# FDC_Board_DualSlim.net
KiCad netlist of a schematic drawn in EAGLE
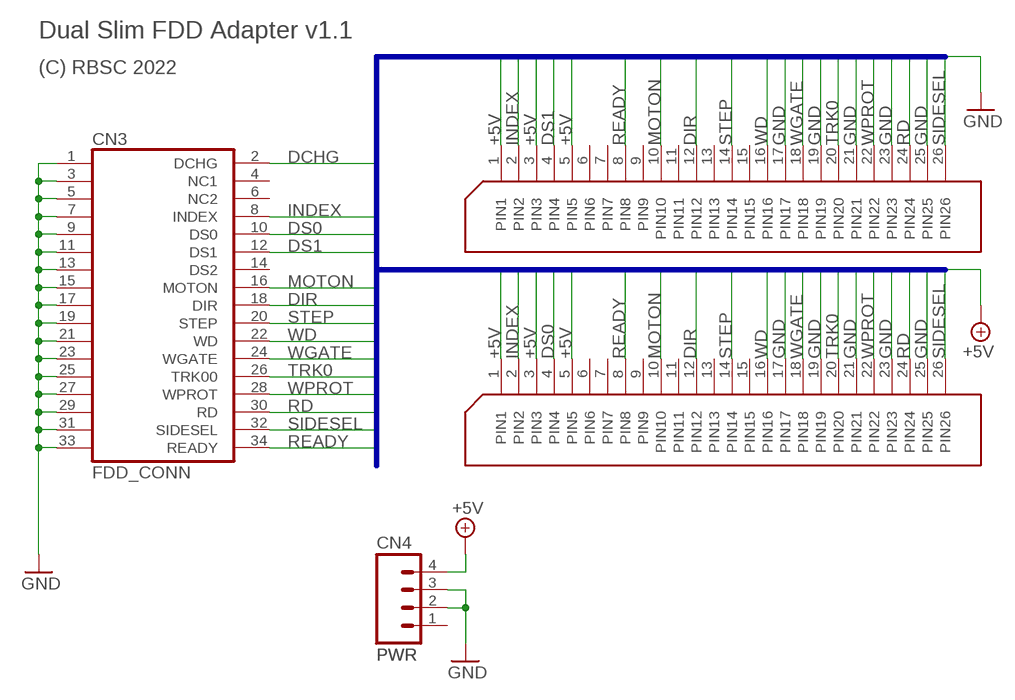
[diagram p0: schematic, sheet 1]

(export (version "E")
  (design (tool "Eeschema 10.0.6"))
  (components
    (comp (ref "CN1")
      (value "FDC_26")
      (footprint "eagle-import:FDC26")
      (libsource (lib "eagle-import") (part "FDC_26"))
    )
    (comp (ref "CN2")
      (value "FDC_26")
      (footprint "eagle-import:FDC26")
      (libsource (lib "eagle-import") (part "FDC_26"))
    )
    (comp (ref "CN3")
      (value "FDD_CONN")
      (footprint "eagle-import:FDD_CONN")
      (libsource (lib "eagle-import") (part "FDD_CONN"))
    )
    (comp (ref "CN4")
      (value "PWR")
      (footprint "eagle-import:1X04_LONGPADS")
      (libsource (lib "eagle-import") (part "M04LONGPADS"))
    )
  )
  (nets
    (net (code "1") (name "+5V") (class "Default")
      (node (ref "CN1") (pin "1") (pinfunction "PIN1_1") (pintype "bidirectional"))
      (node (ref "CN1") (pin "3") (pinfunction "PIN3_3") (pintype "bidirectional"))
      (node (ref "CN1") (pin "5") (pinfunction "PIN5_5") (pintype "bidirectional"))
      (node (ref "CN2") (pin "1") (pinfunction "PIN1_1") (pintype "bidirectional"))
      (node (ref "CN2") (pin "3") (pinfunction "PIN3_3") (pintype "bidirectional"))
      (node (ref "CN2") (pin "5") (pinfunction "PIN5_5") (pintype "bidirectional"))
      (node (ref "CN4") (pin "4") (pinfunction "4_4") (pintype "passive"))
    )
    (net (code "2") (name "/DCHG") (class "Default")
      (node (ref "CN3") (pin "2") (pinfunction "DCHG_2") (pintype "passive"))
    )
    (net (code "3") (name "/DIR") (class "Default")
      (node (ref "CN1") (pin "12") (pinfunction "PIN12_12") (pintype "bidirectional"))
      (node (ref "CN2") (pin "12") (pinfunction "PIN12_12") (pintype "bidirectional"))
      (node (ref "CN3") (pin "18") (pinfunction "DIR_18") (pintype "passive"))
    )
    (net (code "4") (name "/DS0") (class "Default")
      (node (ref "CN1") (pin "4") (pinfunction "PIN4_4") (pintype "bidirectional"))
      (node (ref "CN3") (pin "10") (pinfunction "DS0_10") (pintype "passive"))
    )
    (net (code "5") (name "/DS1") (class "Default")
      (node (ref "CN2") (pin "4") (pinfunction "PIN4_4") (pintype "bidirectional"))
      (node (ref "CN3") (pin "12") (pinfunction "DS1_12") (pintype "passive"))
    )
    (net (code "6") (name "/INDEX") (class "Default")
      (node (ref "CN1") (pin "2") (pinfunction "PIN2_2") (pintype "bidirectional"))
      (node (ref "CN2") (pin "2") (pinfunction "PIN2_2") (pintype "bidirectional"))
      (node (ref "CN3") (pin "8") (pinfunction "INDEX_8") (pintype "passive"))
    )
    (net (code "7") (name "/MOTON") (class "Default")
      (node (ref "CN1") (pin "10") (pinfunction "PIN10_10") (pintype "bidirectional"))
      (node (ref "CN2") (pin "10") (pinfunction "PIN10_10") (pintype "bidirectional"))
      (node (ref "CN3") (pin "16") (pinfunction "MOTON_16") (pintype "passive"))
    )
    (net (code "8") (name "/RD") (class "Default")
      (node (ref "CN1") (pin "24") (pinfunction "PIN24_24") (pintype "bidirectional"))
      (node (ref "CN2") (pin "24") (pinfunction "PIN24_24") (pintype "bidirectional"))
      (node (ref "CN3") (pin "30") (pinfunction "RD_30") (pintype "passive"))
    )
    (net (code "9") (name "/READY") (class "Default")
      (node (ref "CN1") (pin "8") (pinfunction "PIN8_8") (pintype "bidirectional"))
      (node (ref "CN2") (pin "8") (pinfunction "PIN8_8") (pintype "bidirectional"))
      (node (ref "CN3") (pin "34") (pinfunction "READY_34") (pintype "passive"))
    )
    (net (code "10") (name "/SIDESEL") (class "Default")
      (node (ref "CN1") (pin "26") (pinfunction "PIN26_26") (pintype "bidirectional"))
      (node (ref "CN2") (pin "26") (pinfunction "PIN26_26") (pintype "bidirectional"))
      (node (ref "CN3") (pin "32") (pinfunction "SIDESEL_32") (pintype "passive"))
    )
    (net (code "11") (name "/STEP") (class "Default")
      (node (ref "CN1") (pin "14") (pinfunction "PIN14_14") (pintype "bidirectional"))
      (node (ref "CN2") (pin "14") (pinfunction "PIN14_14") (pintype "bidirectional"))
      (node (ref "CN3") (pin "20") (pinfunction "STEP_20") (pintype "passive"))
    )
    (net (code "12") (name "/TRK0") (class "Default")
      (node (ref "CN1") (pin "20") (pinfunction "PIN20_20") (pintype "bidirectional"))
      (node (ref "CN2") (pin "20") (pinfunction "PIN20_20") (pintype "bidirectional"))
      (node (ref "CN3") (pin "26") (pinfunction "TRK00_26") (pintype "passive"))
    )
    (net (code "13") (name "/WD") (class "Default")
      (node (ref "CN1") (pin "16") (pinfunction "PIN16_16") (pintype "bidirectional"))
      (node (ref "CN2") (pin "16") (pinfunction "PIN16_16") (pintype "bidirectional"))
      (node (ref "CN3") (pin "22") (pinfunction "WD_22") (pintype "passive"))
    )
    (net (code "14") (name "/WGATE") (class "Default")
      (node (ref "CN1") (pin "18") (pinfunction "PIN18_18") (pintype "bidirectional"))
      (node (ref "CN2") (pin "18") (pinfunction "PIN18_18") (pintype "bidirectional"))
      (node (ref "CN3") (pin "24") (pinfunction "WGATE_24") (pintype "passive"))
    )
    (net (code "15") (name "/WPROT") (class "Default")
      (node (ref "CN1") (pin "22") (pinfunction "PIN22_22") (pintype "bidirectional"))
      (node (ref "CN2") (pin "22") (pinfunction "PIN22_22") (pintype "bidirectional"))
      (node (ref "CN3") (pin "28") (pinfunction "WPROT_28") (pintype "passive"))
    )
    (net (code "16") (name "GND") (class "Default")
      (node (ref "CN1") (pin "17") (pinfunction "PIN17_17") (pintype "bidirectional"))
      (node (ref "CN1") (pin "19") (pinfunction "PIN19_19") (pintype "bidirectional"))
      (node (ref "CN1") (pin "21") (pinfunction "PIN21_21") (pintype "bidirectional"))
      (node (ref "CN1") (pin "23") (pinfunction "PIN23_23") (pintype "bidirectional"))
      (node (ref "CN1") (pin "25") (pinfunction "PIN25_25") (pintype "bidirectional"))
      (node (ref "CN2") (pin "17") (pinfunction "PIN17_17") (pintype "bidirectional"))
      (node (ref "CN2") (pin "19") (pinfunction "PIN19_19") (pintype "bidirectional"))
      (node (ref "CN2") (pin "21") (pinfunction "PIN21_21") (pintype "bidirectional"))
      (node (ref "CN2") (pin "23") (pinfunction "PIN23_23") (pintype "bidirectional"))
      (node (ref "CN2") (pin "25") (pinfunction "PIN25_25") (pintype "bidirectional"))
      (node (ref "CN3") (pin "1") (pinfunction "1_1") (pintype "passive"))
      (node (ref "CN3") (pin "11") (pinfunction "11_11") (pintype "passive"))
      (node (ref "CN3") (pin "13") (pinfunction "13_13") (pintype "passive"))
      (node (ref "CN3") (pin "15") (pinfunction "15_15") (pintype "passive"))
      (node (ref "CN3") (pin "17") (pinfunction "17_17") (pintype "passive"))
      (node (ref "CN3") (pin "19") (pinfunction "19_19") (pintype "passive"))
      (node (ref "CN3") (pin "21") (pinfunction "21_21") (pintype "passive"))
      (node (ref "CN3") (pin "23") (pinfunction "23_23") (pintype "passive"))
      (node (ref "CN3") (pin "25") (pinfunction "25_25") (pintype "passive"))
      (node (ref "CN3") (pin "27") (pinfunction "27_27") (pintype "passive"))
      (node (ref "CN3") (pin "29") (pinfunction "29_29") (pintype "passive"))
      (node (ref "CN3") (pin "3") (pinfunction "3_3") (pintype "passive"))
      (node (ref "CN3") (pin "31") (pinfunction "31_31") (pintype "passive"))
      (node (ref "CN3") (pin "33") (pinfunction "33_33") (pintype "passive"))
      (node (ref "CN3") (pin "5") (pinfunction "5_5") (pintype "passive"))
      (node (ref "CN3") (pin "7") (pinfunction "7_7") (pintype "passive"))
      (node (ref "CN3") (pin "9") (pinfunction "9_9") (pintype "passive"))
      (node (ref "CN4") (pin "2") (pinfunction "2_2") (pintype "passive"))
      (node (ref "CN4") (pin "3") (pinfunction "3_3") (pintype "passive"))
    )
    (net (code "17") (name "unconnected-(CN1-PIN6-Pad6)") (class "Default")
      (node (ref "CN1") (pin "6") (pinfunction "PIN6_6") (pintype "bidirectional"))
    )
    (net (code "18") (name "unconnected-(CN1-PIN7-Pad7)") (class "Default")
      (node (ref "CN1") (pin "7") (pinfunction "PIN7_7") (pintype "bidirectional"))
    )
    (net (code "19") (name "unconnected-(CN1-PIN9-Pad9)") (class "Default")
      (node (ref "CN1") (pin "9") (pinfunction "PIN9_9") (pintype "bidirectional"))
    )
    (net (code "20") (name "unconnected-(CN1-PIN11-Pad11)") (class "Default")
      (node (ref "CN1") (pin "11") (pinfunction "PIN11_11") (pintype "bidirectional"))
    )
    (net (code "21") (name "unconnected-(CN1-PIN13-Pad13)") (class "Default")
      (node (ref "CN1") (pin "13") (pinfunction "PIN13_13") (pintype "bidirectional"))
    )
    (net (code "22") (name "unconnected-(CN1-PIN15-Pad15)") (class "Default")
      (node (ref "CN1") (pin "15") (pinfunction "PIN15_15") (pintype "bidirectional"))
    )
    (net (code "23") (name "unconnected-(CN2-PIN6-Pad6)") (class "Default")
      (node (ref "CN2") (pin "6") (pinfunction "PIN6_6") (pintype "bidirectional"))
    )
    (net (code "24") (name "unconnected-(CN2-PIN7-Pad7)") (class "Default")
      (node (ref "CN2") (pin "7") (pinfunction "PIN7_7") (pintype "bidirectional"))
    )
    (net (code "25") (name "unconnected-(CN2-PIN9-Pad9)") (class "Default")
      (node (ref "CN2") (pin "9") (pinfunction "PIN9_9") (pintype "bidirectional"))
    )
    (net (code "26") (name "unconnected-(CN2-PIN11-Pad11)") (class "Default")
      (node (ref "CN2") (pin "11") (pinfunction "PIN11_11") (pintype "bidirectional"))
    )
    (net (code "27") (name "unconnected-(CN2-PIN13-Pad13)") (class "Default")
      (node (ref "CN2") (pin "13") (pinfunction "PIN13_13") (pintype "bidirectional"))
    )
    (net (code "28") (name "unconnected-(CN2-PIN15-Pad15)") (class "Default")
      (node (ref "CN2") (pin "15") (pinfunction "PIN15_15") (pintype "bidirectional"))
    )
    (net (code "29") (name "unconnected-(CN3-DS2-Pad14)") (class "Default")
      (node (ref "CN3") (pin "14") (pinfunction "DS2_14") (pintype "passive"))
    )
    (net (code "30") (name "unconnected-(CN3-NC1-Pad4)") (class "Default")
      (node (ref "CN3") (pin "4") (pinfunction "NC1_4") (pintype "no_connect"))
    )
    (net (code "31") (name "unconnected-(CN3-NC2-Pad6)") (class "Default")
      (node (ref "CN3") (pin "6") (pinfunction "NC2_6") (pintype "no_connect"))
    )
    (net (code "32") (name "unconnected-(CN4-Pad1)") (class "Default")
      (node (ref "CN4") (pin "1") (pinfunction "1_1") (pintype "passive"))
    )
  )
)
